# PyNab_Motor_Encoders.net
KiCad netlist of a schematic drawn in Altium Designer
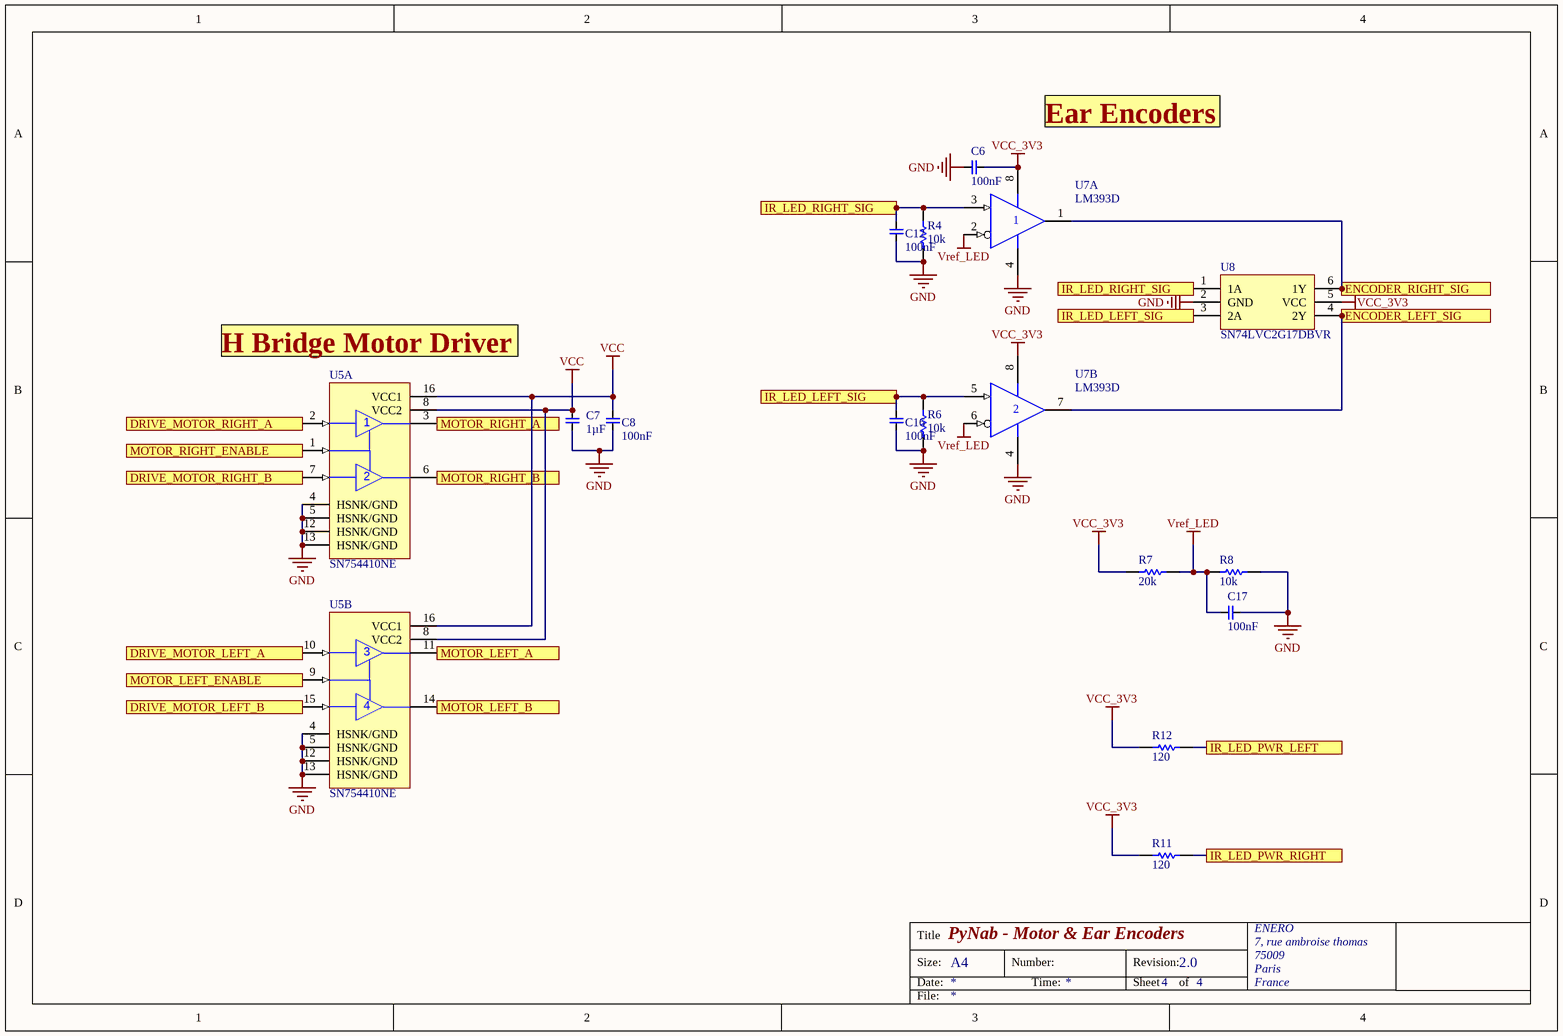
[diagram p0: PyNab_Motor&Encoders.SchDoc]

(export (version "E")
  (design (tool "Eeschema 10.0.6"))
  (components
    (comp (ref "C6")
      (value "100nF")
      (footprint "CAP0603")
      (description "Non-polarised capacitor")
      (libsource (lib "PassiveSMT") (part "Capacitor_np"))
    )
    (comp (ref "C7")
      (value "1µF")
      (footprint "CAP0603")
      (description "Non-polarised capacitor")
      (libsource (lib "PassiveSMT") (part "Capacitor_np"))
    )
    (comp (ref "C8")
      (value "100nF")
      (footprint "CAP0603")
      (description "Non-polarised capacitor")
      (libsource (lib "PassiveSMT") (part "Capacitor_np"))
    )
    (comp (ref "C12")
      (value "100nF")
      (footprint "CAP0603")
      (description "Non-polarised capacitor")
      (libsource (lib "PassiveSMT") (part "Capacitor_np"))
    )
    (comp (ref "C16")
      (value "100nF")
      (footprint "CAP0603")
      (description "Non-polarised capacitor")
      (libsource (lib "PassiveSMT") (part "Capacitor_np"))
    )
    (comp (ref "C17")
      (value "100nF")
      (footprint "CAP0603")
      (description "Non-polarised capacitor")
      (libsource (lib "PassiveSMT") (part "Capacitor_np"))
    )
    (comp (ref "R4")
      (value "10k")
      (footprint "RES0603")
      (description "Resistor")
      (libsource (lib "PassiveSMT") (part "Resistor1"))
    )
    (comp (ref "R6")
      (value "10k")
      (footprint "RES0603")
      (description "Resistor")
      (libsource (lib "PassiveSMT") (part "Resistor1"))
    )
    (comp (ref "R7")
      (value "20k")
      (footprint "RES0603")
      (description "Resistor")
      (libsource (lib "PassiveSMT") (part "Resistor1"))
    )
    (comp (ref "R8")
      (value "10k")
      (footprint "RES0603")
      (description "Resistor")
      (libsource (lib "PassiveSMT") (part "Resistor1"))
    )
    (comp (ref "R11")
      (value "120")
      (footprint "RES0603")
      (description "Resistor")
      (libsource (lib "PassiveSMT") (part "Resistor1"))
    )
    (comp (ref "R12")
      (value "120")
      (footprint "RES0603")
      (description "Resistor")
      (libsource (lib "PassiveSMT") (part "Resistor1"))
    )
    (comp (ref "U5")
      (value "SN754410NE")
      (footprint "DIP16_traversant_support")
      (description "Quadruple Half-H Driver")
      (fields (field (name "PUBLISHER") "Altium Limited"))
      (libsource (lib "TI Interface Peripheral Driver") (part "SN754410NE"))
    )
    (comp (ref "U7")
      (value "LM393D")
      (footprint "D008_N")
      (description "Dual Differential Comparator")
      (fields (field (name "PUBLISHER") "Altium Limited"))
      (libsource (lib "TI Logic Comparator") (part "LM393D"))
    )
    (comp (ref "U8")
      (value "SN74LVC2G17DBVR")
      (footprint "SN74LVC2G17DBVR")
      (libsource (lib "SN74LVC2G17DBVR") (part "SN74LVC2G17DBVR"))
    )
  )
  (nets
    (net (code "1") (name "/DRIVE_MOTOR_LEFT_A") (class "Default")
      (node (ref "U5") (pin "10") (pinfunction "3A_10") (pintype "input"))
    )
    (net (code "2") (name "/DRIVE_MOTOR_LEFT_B") (class "Default")
      (node (ref "U5") (pin "15") (pinfunction "4A_15") (pintype "input"))
    )
    (net (code "3") (name "/DRIVE_MOTOR_RIGHT_A") (class "Default")
      (node (ref "U5") (pin "2") (pinfunction "1A_2") (pintype "input"))
    )
    (net (code "4") (name "/DRIVE_MOTOR_RIGHT_B") (class "Default")
      (node (ref "U5") (pin "7") (pinfunction "2A_7") (pintype "input"))
    )
    (net (code "5") (name "/ENCODER_LEFT_SIG") (class "Default")
      (node (ref "U7") (pin "7") (pinfunction "OUT_7") (pintype "open_collector"))
      (node (ref "U8") (pin "4") (pinfunction "2Y_4") (pintype "passive"))
    )
    (net (code "6") (name "/ENCODER_RIGHT_SIG") (class "Default")
      (node (ref "U7") (pin "1") (pinfunction "OUT_1") (pintype "open_collector"))
      (node (ref "U8") (pin "6") (pinfunction "1Y_6") (pintype "passive"))
    )
    (net (code "7") (name "/IR_LED_LEFT_SIG") (class "Default")
      (node (ref "C16") (pin "2") (pinfunction "2_2") (pintype "passive"))
      (node (ref "R6") (pin "2") (pinfunction "2_2") (pintype "passive"))
      (node (ref "U7") (pin "5") (pinfunction "IN+_5") (pintype "input"))
      (node (ref "U8") (pin "3") (pinfunction "2A_3") (pintype "passive"))
    )
    (net (code "8") (name "/IR_LED_PWR_LEFT") (class "Default")
      (node (ref "R12") (pin "2") (pinfunction "2_2") (pintype "passive"))
    )
    (net (code "9") (name "/IR_LED_PWR_RIGHT") (class "Default")
      (node (ref "R11") (pin "2") (pinfunction "2_2") (pintype "passive"))
    )
    (net (code "10") (name "/IR_LED_RIGHT_SIG") (class "Default")
      (node (ref "C12") (pin "2") (pinfunction "2_2") (pintype "passive"))
      (node (ref "R4") (pin "2") (pinfunction "2_2") (pintype "passive"))
      (node (ref "U7") (pin "3") (pinfunction "IN+_3") (pintype "input"))
      (node (ref "U8") (pin "1") (pinfunction "1A_1") (pintype "passive"))
    )
    (net (code "11") (name "/MOTOR_LEFT_A") (class "Default")
      (node (ref "U5") (pin "11") (pinfunction "3Y_11") (pintype "tri_state"))
    )
    (net (code "12") (name "/MOTOR_LEFT_B") (class "Default")
      (node (ref "U5") (pin "14") (pinfunction "4Y_14") (pintype "tri_state"))
    )
    (net (code "13") (name "/MOTOR_LEFT_ENABLE") (class "Default")
      (node (ref "U5") (pin "9") (pinfunction "3,4EN_9") (pintype "input"))
    )
    (net (code "14") (name "/MOTOR_RIGHT_A") (class "Default")
      (node (ref "U5") (pin "3") (pinfunction "1Y_3") (pintype "tri_state"))
    )
    (net (code "15") (name "/MOTOR_RIGHT_B") (class "Default")
      (node (ref "U5") (pin "6") (pinfunction "2Y_6") (pintype "tri_state"))
    )
    (net (code "16") (name "/MOTOR_RIGHT_ENABLE") (class "Default")
      (node (ref "U5") (pin "1") (pinfunction "1,2EN_1") (pintype "input"))
    )
    (net (code "17") (name "GND") (class "Default")
      (node (ref "C12") (pin "1") (pinfunction "1_1") (pintype "passive"))
      (node (ref "C16") (pin "1") (pinfunction "1_1") (pintype "passive"))
      (node (ref "C17") (pin "2") (pinfunction "2_2") (pintype "passive"))
      (node (ref "C6") (pin "2") (pinfunction "2_2") (pintype "passive"))
      (node (ref "C7") (pin "1") (pinfunction "1_1") (pintype "passive"))
      (node (ref "C8") (pin "1") (pinfunction "1_1") (pintype "passive"))
      (node (ref "R4") (pin "1") (pinfunction "1_1") (pintype "passive"))
      (node (ref "R6") (pin "1") (pinfunction "1_1") (pintype "passive"))
      (node (ref "R8") (pin "2") (pinfunction "2_2") (pintype "passive"))
      (node (ref "U5") (pin "12") (pinfunction "HSNK/GND_12") (pintype "power_in"))
      (node (ref "U5") (pin "13") (pinfunction "HSNK/GND_13") (pintype "power_in"))
      (node (ref "U5") (pin "4") (pinfunction "HSNK/GND_4") (pintype "power_in"))
      (node (ref "U5") (pin "5") (pinfunction "HSNK/GND_5") (pintype "power_in"))
      (node (ref "U7") (pin "4") (pinfunction "GND_4") (pintype "power_in"))
      (node (ref "U8") (pin "2") (pinfunction "GND_2") (pintype "power_in"))
    )
    (net (code "18") (name "VCC") (class "Default")
      (node (ref "C7") (pin "2") (pinfunction "2_2") (pintype "passive"))
      (node (ref "C8") (pin "2") (pinfunction "2_2") (pintype "passive"))
      (node (ref "U5") (pin "16") (pinfunction "VCC1_16") (pintype "power_in"))
      (node (ref "U5") (pin "8") (pinfunction "VCC2_8") (pintype "power_in"))
    )
    (net (code "19") (name "VCC_3V3") (class "Default")
      (node (ref "C6") (pin "1") (pinfunction "1_1") (pintype "passive"))
      (node (ref "R11") (pin "1") (pinfunction "1_1") (pintype "passive"))
      (node (ref "R12") (pin "1") (pinfunction "1_1") (pintype "passive"))
      (node (ref "R7") (pin "1") (pinfunction "1_1") (pintype "passive"))
      (node (ref "U7") (pin "8") (pinfunction "VCC_8") (pintype "power_in"))
      (node (ref "U8") (pin "5") (pinfunction "VCC_5") (pintype "passive"))
    )
    (net (code "20") (name "Vref_LED") (class "Default")
      (node (ref "C17") (pin "1") (pinfunction "1_1") (pintype "passive"))
      (node (ref "R7") (pin "2") (pinfunction "2_2") (pintype "passive"))
      (node (ref "R8") (pin "1") (pinfunction "1_1") (pintype "passive"))
      (node (ref "U7") (pin "2") (pinfunction "IN-_2") (pintype "input"))
      (node (ref "U7") (pin "6") (pinfunction "IN-_6") (pintype "input"))
    )
  )
)
